# 08_-_ETH1-100.net
KiCad netlist of a schematic drawn in Altium Designer
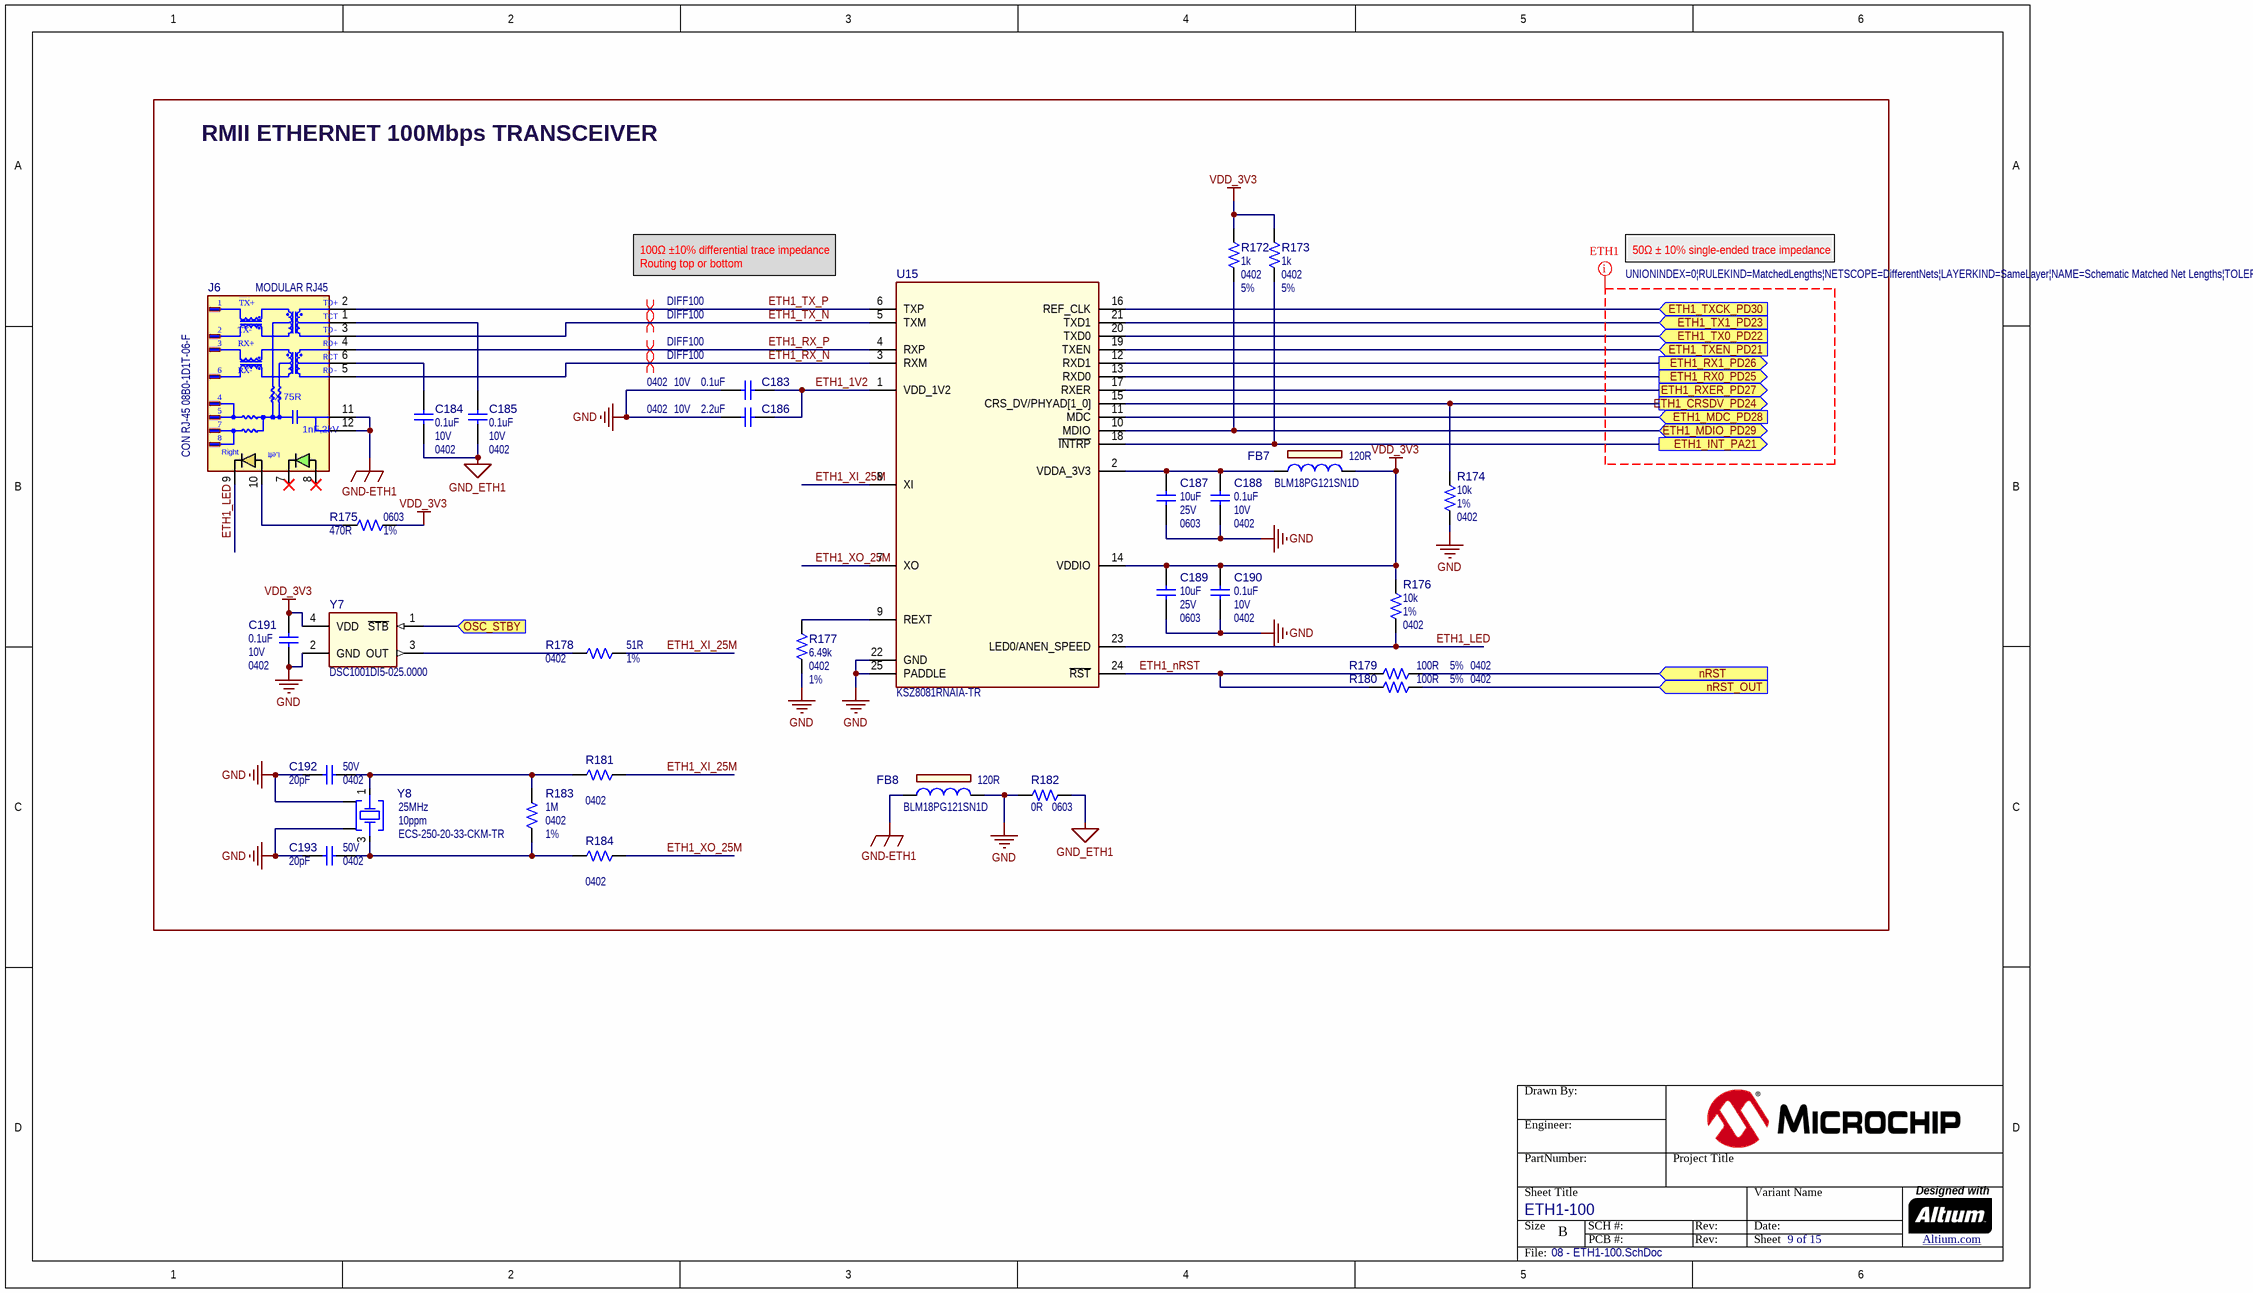
[diagram p0: 08 - ETH1-100.SchDoc]

(export (version "E")
  (design (tool "Eeschema 10.0.6"))
  (components
    (comp (ref "C183")
      (value "0.1uF")
      (footprint "CAP_C_0402")
      (description "Capacitor")
      (fields
        (field (name "VOLTAGE") "10V")
        (field (name "PACKAGE") "0402")
        (field (name "TOLERANCE") "10%")
        (field (name "Comment") "Capacitor NP")
        (field (name "OWNER") "Tad Ahlvers")
      )
      (libsource (lib "MCHP-CDB") (part "Capacitor NP"))
    )
    (comp (ref "C184")
      (value "0.1uF")
      (footprint "CAP_C_0402")
      (description "Capacitor")
      (fields
        (field (name "VOLTAGE") "10V")
        (field (name "PACKAGE") "0402")
        (field (name "TOLERANCE") "10%")
        (field (name "Comment") "Capacitor NP")
        (field (name "OWNER") "Tad Ahlvers")
      )
      (libsource (lib "MCHP-CDB") (part "Capacitor NP"))
    )
    (comp (ref "C185")
      (value "0.1uF")
      (footprint "CAP_C_0402")
      (description "Capacitor")
      (fields
        (field (name "VOLTAGE") "10V")
        (field (name "PACKAGE") "0402")
        (field (name "TOLERANCE") "10%")
        (field (name "Comment") "Capacitor NP")
        (field (name "OWNER") "Tad Ahlvers")
      )
      (libsource (lib "MCHP-CDB") (part "Capacitor NP"))
    )
    (comp (ref "C186")
      (value "2.2uF")
      (footprint "CAP_C_0402")
      (description "Capacitor")
      (fields
        (field (name "VOLTAGE") "10V")
        (field (name "PACKAGE") "0402")
        (field (name "TOLERANCE") "10%")
        (field (name "Comment") "Capacitor NP")
        (field (name "OWNER") "Sorin Stanoaia")
      )
      (libsource (lib "MCHP-CDB") (part "Capacitor NP"))
    )
    (comp (ref "C187")
      (value "10uF")
      (footprint "CAP_C_0603")
      (description "Capacitor")
      (fields
        (field (name "VOLTAGE") "25V")
        (field (name "PACKAGE") "0603")
        (field (name "TOLERANCE") "20%")
        (field (name "Comment") "Capacitor NP")
        (field (name "OWNER") "Razvan Cristescu")
      )
      (libsource (lib "MCHP-CDB") (part "Capacitor NP"))
    )
    (comp (ref "C188")
      (value "0.1uF")
      (footprint "CAP_C_0402")
      (description "Capacitor")
      (fields
        (field (name "VOLTAGE") "10V")
        (field (name "PACKAGE") "0402")
        (field (name "TOLERANCE") "10%")
        (field (name "Comment") "Capacitor NP")
        (field (name "OWNER") "Tad Ahlvers")
      )
      (libsource (lib "MCHP-CDB") (part "Capacitor NP"))
    )
    (comp (ref "C189")
      (value "10uF")
      (footprint "CAP_C_0603")
      (description "Capacitor")
      (fields
        (field (name "VOLTAGE") "25V")
        (field (name "PACKAGE") "0603")
        (field (name "TOLERANCE") "20%")
        (field (name "Comment") "Capacitor NP")
        (field (name "OWNER") "Razvan Cristescu")
      )
      (libsource (lib "MCHP-CDB") (part "Capacitor NP"))
    )
    (comp (ref "C190")
      (value "0.1uF")
      (footprint "CAP_C_0402")
      (description "Capacitor")
      (fields
        (field (name "VOLTAGE") "10V")
        (field (name "PACKAGE") "0402")
        (field (name "TOLERANCE") "10%")
        (field (name "Comment") "Capacitor NP")
        (field (name "OWNER") "Tad Ahlvers")
      )
      (libsource (lib "MCHP-CDB") (part "Capacitor NP"))
    )
    (comp (ref "C191")
      (value "0.1uF")
      (footprint "CAP_C_0402")
      (description "Capacitor")
      (fields
        (field (name "VOLTAGE") "10V")
        (field (name "PACKAGE") "0402")
        (field (name "TOLERANCE") "10%")
        (field (name "Comment") "Capacitor NP")
        (field (name "OWNER") "Tad Ahlvers")
      )
      (libsource (lib "MCHP-CDB") (part "Capacitor NP"))
    )
    (comp (ref "C192")
      (value "20pF")
      (footprint "CAP_C_0402")
      (fields
        (field (name "VOLTAGE") "50V")
        (field (name "PACKAGE") "0402")
        (field (name "TOLERANCE") "2%")
        (field (name "Comment") "Capacitor NP")
        (field (name "OWNER") "Dragos Danaila")
      )
      (libsource (lib "") (part "Capacitor NP_1"))
    )
    (comp (ref "C193")
      (value "20pF")
      (footprint "CAP_C_0402")
      (fields
        (field (name "VOLTAGE") "50V")
        (field (name "PACKAGE") "0402")
        (field (name "TOLERANCE") "2%")
        (field (name "Comment") "Capacitor NP")
        (field (name "OWNER") "Dragos Danaila")
      )
      (libsource (lib "") (part "Capacitor NP_1"))
    )
    (comp (ref "FB7")
      (value "120R")
      (footprint "IND_C_0603")
      (fields
        (field (name "MANUFACTURER PART NUMBER 1") "BLM18PG121SN1D")
        (field (name "Comment") "Ferrite Bead")
        (field (name "OWNER") "Petnarong Chaijaroong")
      )
      (libsource (lib "MCHP-CDB") (part "Ferrite Bead"))
    )
    (comp (ref "FB8")
      (value "120R")
      (footprint "IND_C_0603")
      (fields
        (field (name "MANUFACTURER PART NUMBER 1") "BLM18PG121SN1D")
        (field (name "Comment") "Ferrite Bead")
        (field (name "OWNER") "Petnarong Chaijaroong")
      )
      (libsource (lib "MCHP-CDB") (part "Ferrite Bead"))
    )
    (comp (ref "J6")
      (value "CON RJ-45 08B0-1D1T-06-F")
      (footprint "CON_JACK_RJ45_RA_08B0-1D1T-06-F")
      (description "100 Base-TX (Fast Ethernet), RJ45 1x1 Tab-UP with LEDs(g/y), integrated magnetics connector")
      (fields (field (name "ALTIUM_VALUE") "MODULAR RJ45") (field (name "OWNER") "Ilie Galan"))
      (libsource (lib "MCHP-CDB") (part "CON RJ-45 08B0-1D1T-06-F"))
    )
    (comp (ref "R172")
      (value "1k")
      (footprint "RES_C_0402")
      (description "Resistor")
      (fields
        (field (name "PACKAGE") "0402")
        (field (name "TOLERANCE") "5%")
        (field (name "VOLTAGE") "50V")
        (field (name "POWER") "1/16W")
        (field (name "OWNER") "Tad Ahlvers")
      )
      (libsource (lib "MCHP-CDB") (part "Resistor"))
    )
    (comp (ref "R173")
      (value "1k")
      (footprint "RES_C_0402")
      (description "Resistor")
      (fields
        (field (name "PACKAGE") "0402")
        (field (name "TOLERANCE") "5%")
        (field (name "VOLTAGE") "50V")
        (field (name "POWER") "1/16W")
        (field (name "OWNER") "Tad Ahlvers")
      )
      (libsource (lib "MCHP-CDB") (part "Resistor"))
    )
    (comp (ref "R174")
      (value "10k")
      (footprint "RES_C_0402")
      (description "Resistor")
      (fields
        (field (name "PACKAGE") "0402")
        (field (name "TOLERANCE") "1%")
        (field (name "VOLTAGE") "50V")
        (field (name "POWER") "1/10W")
        (field (name "OWNER") "Brent Lanphear")
      )
      (libsource (lib "MCHP-CDB") (part "Resistor"))
    )
    (comp (ref "R175")
      (value "470R")
      (footprint "RES_C_0603")
      (description "Resistor")
      (fields
        (field (name "PACKAGE") "0603")
        (field (name "TOLERANCE") "1%")
        (field (name "VOLTAGE") "50V")
        (field (name "POWER") "1/10W")
      )
      (libsource (lib "MCHP-CDB") (part "Resistor"))
    )
    (comp (ref "R176")
      (value "10k")
      (footprint "RES_C_0402")
      (description "Resistor")
      (fields
        (field (name "PACKAGE") "0402")
        (field (name "TOLERANCE") "1%")
        (field (name "VOLTAGE") "50V")
        (field (name "POWER") "1/10W")
        (field (name "OWNER") "Brent Lanphear")
      )
      (libsource (lib "MCHP-CDB") (part "Resistor"))
    )
    (comp (ref "R177")
      (value "6.49k")
      (footprint "RES_C_0402")
      (description "Resistor")
      (fields
        (field (name "PACKAGE") "0402")
        (field (name "TOLERANCE") "1%")
        (field (name "VOLTAGE") "50V")
        (field (name "POWER") "1/16W")
        (field (name "OWNER") "Dragos Danaila")
      )
      (libsource (lib "MCHP-CDB") (part "Resistor"))
    )
    (comp (ref "R178")
      (value "51R")
      (footprint "RES_C_0402")
      (description "Resistor")
      (fields
        (field (name "PACKAGE") "0402")
        (field (name "TOLERANCE") "1%")
        (field (name "VOLTAGE") "50V")
        (field (name "POWER") "1/5W")
        (field (name "OWNER") "Dragos Danaila")
      )
      (libsource (lib "MCHP-CDB") (part "Resistor"))
    )
    (comp (ref "R179")
      (value "100R")
      (footprint "RES_C_0402")
      (description "Resistor")
      (fields
        (field (name "PACKAGE") "0402")
        (field (name "TOLERANCE") "5%")
        (field (name "VOLTAGE") "50V")
        (field (name "POWER") "1/16W")
        (field (name "OWNER") "Dragos Danaila")
      )
      (libsource (lib "MCHP-CDB") (part "Resistor"))
    )
    (comp (ref "R180")
      (value "100R")
      (footprint "RES_C_0402")
      (description "Resistor")
      (fields
        (field (name "PACKAGE") "0402")
        (field (name "TOLERANCE") "5%")
        (field (name "VOLTAGE") "50V")
        (field (name "POWER") "1/16W")
        (field (name "OWNER") "Dragos Danaila")
      )
      (libsource (lib "MCHP-CDB") (part "Resistor"))
    )
    (comp (ref "R181")
      (value "Resistor")
      (footprint "RES_C_0402")
      (fields
        (field (name "PACKAGE") "0402")
        (field (name "POWER") "1/16W")
        (field (name "VOLTAGE") "50V")
        (field (name "OWNER") "Dragos Danaila")
      )
      (libsource (lib "MCHP-CDB") (part "Resistor"))
    )
    (comp (ref "R182")
      (value "0R")
      (footprint "RES_C_0603")
      (description "Resistor")
      (fields (field (name "PACKAGE") "0603") (field (name "POWER") "1/10W"))
      (libsource (lib "MCHP-CDB") (part "Resistor"))
    )
    (comp (ref "R183")
      (value "1M")
      (footprint "RES_C_0402")
      (description "Resistor")
      (fields
        (field (name "PACKAGE") "0402")
        (field (name "TOLERANCE") "1%")
        (field (name "VOLTAGE") "50V")
        (field (name "POWER") "1/10W")
        (field (name "OWNER") "Brent Lanphear")
      )
      (libsource (lib "MCHP-CDB") (part "Resistor"))
    )
    (comp (ref "R184")
      (value "Resistor")
      (footprint "RES_C_0402")
      (fields
        (field (name "PACKAGE") "0402")
        (field (name "POWER") "1/16W")
        (field (name "VOLTAGE") "50V")
        (field (name "OWNER") "Dragos Danaila")
      )
      (libsource (lib "MCHP-CDB") (part "Resistor"))
    )
    (comp (ref "U15")
      (value "KSZ8081RNAIA-TR")
      (footprint "QFN-24_4X4")
      (fields (field (name "Comment") "ETHERNET QFN-24") (field (name "OWNER") "Ciprian Abramov"))
      (libsource (lib "MCHP-CDB") (part "KSZ8081RNAIA QFN-24"))
    )
    (comp (ref "Y7")
      (value "DSC10xx DFN-4")
      (footprint "DFN-4_2.5x2")
      (fields
        (field (name "MANUFACTURER PART NUMBER 1") "DSC1001DI5-025.0000")
        (field (name "OWNER") "Ciprian Abramov")
      )
      (libsource (lib "MCHP-CDB") (part "DSC10xx DFN-4"))
    )
    (comp (ref "Y8")
      (value "25MHz")
      (footprint "CRYSTAL_L3.2W2.5H0.8")
      (description "Crystal")
      (fields
        (field (name "TOLERANCE") "10ppm")
        (field (name "MANUFACTURER PART NUMBER 1") "ECS-250-20-33-CKM-TR")
        (field (name "Comment") "Crystal 4 pins 1-3")
        (field (name "OWNER") "Ciprian Abramov")
      )
      (libsource (lib "MCHP-CDB") (part "Crystal 4 pins 1-3"))
    )
  )
  (nets
    (net (code "1") (name "/ETH1_1V2") (class "Default")
      (node (ref "C183") (pin "2") (pinfunction "2_2") (pintype "passive"))
      (node (ref "C186") (pin "2") (pinfunction "2_2") (pintype "passive"))
      (node (ref "U15") (pin "1") (pinfunction "VDD_1V2_1") (pintype "passive"))
    )
    (net (code "2") (name "/ETH1_CRSDV_PD24") (class "Default")
      (node (ref "R174") (pin "2") (pinfunction "2_2") (pintype "passive"))
      (node (ref "U15") (pin "15") (pinfunction "CRS_DV/PHYAD[1_0]_15") (pintype "passive"))
    )
    (net (code "3") (name "/ETH1_INT_PA21") (class "Default")
      (node (ref "R173") (pin "1") (pinfunction "1_1") (pintype "passive"))
      (node (ref "U15") (pin "18") (pinfunction "~{INTRP}_18") (pintype "passive"))
    )
    (net (code "4") (name "/ETH1_LED") (class "Default")
      (node (ref "J6") (pin "9") (pinfunction "Ag_9") (pintype "passive"))
      (node (ref "R176") (pin "1") (pinfunction "1_1") (pintype "passive"))
      (node (ref "U15") (pin "23") (pinfunction "LED0/ANEN_SPEED_23") (pintype "passive"))
    )
    (net (code "5") (name "/ETH1_MDC_PD28") (class "Default")
      (node (ref "U15") (pin "11") (pinfunction "MDC_11") (pintype "passive"))
    )
    (net (code "6") (name "/ETH1_MDIO_PD29") (class "Default")
      (node (ref "R172") (pin "1") (pinfunction "1_1") (pintype "passive"))
      (node (ref "U15") (pin "10") (pinfunction "MDIO_10") (pintype "passive"))
    )
    (net (code "7") (name "/ETH1_RX0_PD25") (class "Default")
      (node (ref "U15") (pin "13") (pinfunction "RXD0_13") (pintype "passive"))
    )
    (net (code "8") (name "/ETH1_RX1_PD26") (class "Default")
      (node (ref "U15") (pin "12") (pinfunction "RXD1_12") (pintype "passive"))
    )
    (net (code "9") (name "/ETH1_RXER_PD27") (class "Default")
      (node (ref "U15") (pin "17") (pinfunction "RXER_17") (pintype "passive"))
    )
    (net (code "10") (name "/ETH1_RX_N") (class "Default")
      (node (ref "J6") (pin "5") (pinfunction "RD-_5") (pintype "passive"))
      (node (ref "U15") (pin "3") (pinfunction "RXM_3") (pintype "passive"))
    )
    (net (code "11") (name "/ETH1_RX_P") (class "Default")
      (node (ref "J6") (pin "4") (pinfunction "RD+_4") (pintype "passive"))
      (node (ref "U15") (pin "4") (pinfunction "RXP_4") (pintype "passive"))
    )
    (net (code "12") (name "/ETH1_TX0_PD22") (class "Default")
      (node (ref "U15") (pin "20") (pinfunction "TXD0_20") (pintype "passive"))
    )
    (net (code "13") (name "/ETH1_TX1_PD23") (class "Default")
      (node (ref "U15") (pin "21") (pinfunction "TXD1_21") (pintype "passive"))
    )
    (net (code "14") (name "/ETH1_TXCK_PD30") (class "Default")
      (node (ref "U15") (pin "16") (pinfunction "REF_CLK_16") (pintype "passive"))
    )
    (net (code "15") (name "/ETH1_TXEN_PD21") (class "Default")
      (node (ref "U15") (pin "19") (pinfunction "TXEN_19") (pintype "passive"))
    )
    (net (code "16") (name "/ETH1_TX_N") (class "Default")
      (node (ref "J6") (pin "3") (pinfunction "TD-_3") (pintype "passive"))
      (node (ref "U15") (pin "5") (pinfunction "TXM_5") (pintype "passive"))
    )
    (net (code "17") (name "/ETH1_TX_P") (class "Default")
      (node (ref "J6") (pin "2") (pinfunction "TD+_2") (pintype "passive"))
      (node (ref "U15") (pin "6") (pinfunction "TXP_6") (pintype "passive"))
    )
    (net (code "18") (name "/ETH1_XI_25M") (class "Default")
      (node (ref "R178") (pin "2") (pinfunction "2_2") (pintype "passive"))
      (node (ref "R181") (pin "2") (pinfunction "2_2") (pintype "passive"))
      (node (ref "U15") (pin "8") (pinfunction "XI_8") (pintype "passive"))
    )
    (net (code "19") (name "/ETH1_XO_25M") (class "Default")
      (node (ref "R184") (pin "2") (pinfunction "2_2") (pintype "passive"))
      (node (ref "U15") (pin "7") (pinfunction "XO_7") (pintype "passive"))
    )
    (net (code "20") (name "/ETH1_nRST") (class "Default")
      (node (ref "R179") (pin "1") (pinfunction "1_1") (pintype "passive"))
      (node (ref "R180") (pin "1") (pinfunction "1_1") (pintype "passive"))
      (node (ref "U15") (pin "24") (pinfunction "~{RST}_24") (pintype "passive"))
    )
    (net (code "21") (name "/OSC_STBY") (class "Default")
      (node (ref "Y7") (pin "1") (pinfunction "~{STB}_1") (pintype "input"))
    )
    (net (code "22") (name "/nRST") (class "Default")
      (node (ref "R179") (pin "2") (pinfunction "2_2") (pintype "passive"))
    )
    (net (code "23") (name "/nRST_OUT") (class "Default")
      (node (ref "R180") (pin "2") (pinfunction "2_2") (pintype "passive"))
    )
    (net (code "24") (name "GND") (class "Default")
      (node (ref "C183") (pin "1") (pinfunction "1_1") (pintype "passive"))
      (node (ref "C186") (pin "1") (pinfunction "1_1") (pintype "passive"))
      (node (ref "C187") (pin "2") (pinfunction "2_2") (pintype "passive"))
      (node (ref "C188") (pin "1") (pinfunction "1_1") (pintype "passive"))
      (node (ref "C189") (pin "2") (pinfunction "2_2") (pintype "passive"))
      (node (ref "C190") (pin "1") (pinfunction "1_1") (pintype "passive"))
      (node (ref "C191") (pin "1") (pinfunction "1_1") (pintype "passive"))
      (node (ref "C192") (pin "2") (pinfunction "2_2") (pintype "passive"))
      (node (ref "C193") (pin "2") (pinfunction "2_2") (pintype "passive"))
      (node (ref "FB8") (pin "2") (pinfunction "2_2") (pintype "passive"))
      (node (ref "R174") (pin "1") (pinfunction "1_1") (pintype "passive"))
      (node (ref "R177") (pin "1") (pinfunction "1_1") (pintype "passive"))
      (node (ref "R182") (pin "1") (pinfunction "1_1") (pintype "passive"))
      (node (ref "U15") (pin "22") (pinfunction "GND_22") (pintype "passive"))
      (node (ref "U15") (pin "25") (pinfunction "PADDLE_25") (pintype "passive"))
      (node (ref "Y7") (pin "2") (pinfunction "GND_2") (pintype "power_in"))
      (node (ref "Y8") (pin "2") (pintype "passive"))
      (node (ref "Y8") (pin "4") (pintype "passive"))
    )
    (net (code "25") (name "GND-ETH1") (class "Default")
      (node (ref "FB8") (pin "1") (pinfunction "1_1") (pintype "passive"))
      (node (ref "J6") (pin "11") (pinfunction "SHLD_11") (pintype "passive"))
      (node (ref "J6") (pin "12") (pinfunction "SHLD_12") (pintype "passive"))
    )
    (net (code "26") (name "GND_ETH1") (class "Default")
      (node (ref "C184") (pin "1") (pinfunction "1_1") (pintype "passive"))
      (node (ref "C185") (pin "1") (pinfunction "1_1") (pintype "passive"))
      (node (ref "R182") (pin "2") (pinfunction "2_2") (pintype "passive"))
    )
    (net (code "27") (name "Net-(C192-Pad1)") (class "Default")
      (node (ref "C192") (pin "1") (pinfunction "1_1") (pintype "passive"))
      (node (ref "R181") (pin "1") (pinfunction "1_1") (pintype "passive"))
      (node (ref "R183") (pin "2") (pinfunction "2_2") (pintype "passive"))
      (node (ref "Y8") (pin "1") (pintype "passive"))
    )
    (net (code "28") (name "Net-(C193-Pad1)") (class "Default")
      (node (ref "C193") (pin "1") (pinfunction "1_1") (pintype "passive"))
      (node (ref "R183") (pin "1") (pinfunction "1_1") (pintype "passive"))
      (node (ref "R184") (pin "1") (pinfunction "1_1") (pintype "passive"))
      (node (ref "Y8") (pin "3") (pintype "passive"))
    )
    (net (code "29") (name "Net-(J6-Cg)") (class "Default")
      (node (ref "J6") (pin "10") (pinfunction "Cg_10") (pintype "passive"))
      (node (ref "R175") (pin "2") (pinfunction "2_2") (pintype "passive"))
    )
    (net (code "30") (name "Net-(J6-RCT)") (class "Default")
      (node (ref "C184") (pin "2") (pinfunction "2_2") (pintype "passive"))
      (node (ref "J6") (pin "6") (pinfunction "RCT_6") (pintype "passive"))
    )
    (net (code "31") (name "Net-(J6-TCT)") (class "Default")
      (node (ref "C185") (pin "2") (pinfunction "2_2") (pintype "passive"))
      (node (ref "J6") (pin "1") (pinfunction "TCT_1") (pintype "passive"))
    )
    (net (code "32") (name "Net-(U15-REXT)") (class "Default")
      (node (ref "R177") (pin "2") (pinfunction "2_2") (pintype "passive"))
      (node (ref "U15") (pin "9") (pinfunction "REXT_9") (pintype "passive"))
    )
    (net (code "33") (name "Net-(U15-VDDA_3V3)") (class "Default")
      (node (ref "C187") (pin "1") (pinfunction "1_1") (pintype "passive"))
      (node (ref "C188") (pin "2") (pinfunction "2_2") (pintype "passive"))
      (node (ref "FB7") (pin "1") (pinfunction "1_1") (pintype "passive"))
      (node (ref "U15") (pin "2") (pinfunction "VDDA_3V3_2") (pintype "passive"))
    )
    (net (code "34") (name "Net-(Y7-OUT)") (class "Default")
      (node (ref "R178") (pin "1") (pinfunction "1_1") (pintype "passive"))
      (node (ref "Y7") (pin "3") (pinfunction "OUT_3") (pintype "output"))
    )
    (net (code "35") (name "VDD_3V3") (class "Default")
      (node (ref "C189") (pin "1") (pinfunction "1_1") (pintype "passive"))
      (node (ref "C190") (pin "2") (pinfunction "2_2") (pintype "passive"))
      (node (ref "C191") (pin "2") (pinfunction "2_2") (pintype "passive"))
      (node (ref "FB7") (pin "2") (pinfunction "2_2") (pintype "passive"))
      (node (ref "R172") (pin "2") (pinfunction "2_2") (pintype "passive"))
      (node (ref "R173") (pin "2") (pinfunction "2_2") (pintype "passive"))
      (node (ref "R175") (pin "1") (pinfunction "1_1") (pintype "passive"))
      (node (ref "R176") (pin "2") (pinfunction "2_2") (pintype "passive"))
      (node (ref "U15") (pin "14") (pinfunction "VDDIO_14") (pintype "passive"))
      (node (ref "Y7") (pin "4") (pinfunction "VDD_4") (pintype "power_in"))
    )
    (net (code "36") (name "unconnected-(J6-Ay-Pad8)") (class "Default")
      (node (ref "J6") (pin "8") (pinfunction "Ay_8") (pintype "passive+no_connect"))
    )
    (net (code "37") (name "unconnected-(J6-Cy-Pad7)") (class "Default")
      (node (ref "J6") (pin "7") (pinfunction "Cy_7") (pintype "passive+no_connect"))
    )
  )
)
